# WiFi_Switch.net
KiCad netlist of a schematic drawn in EAGLE
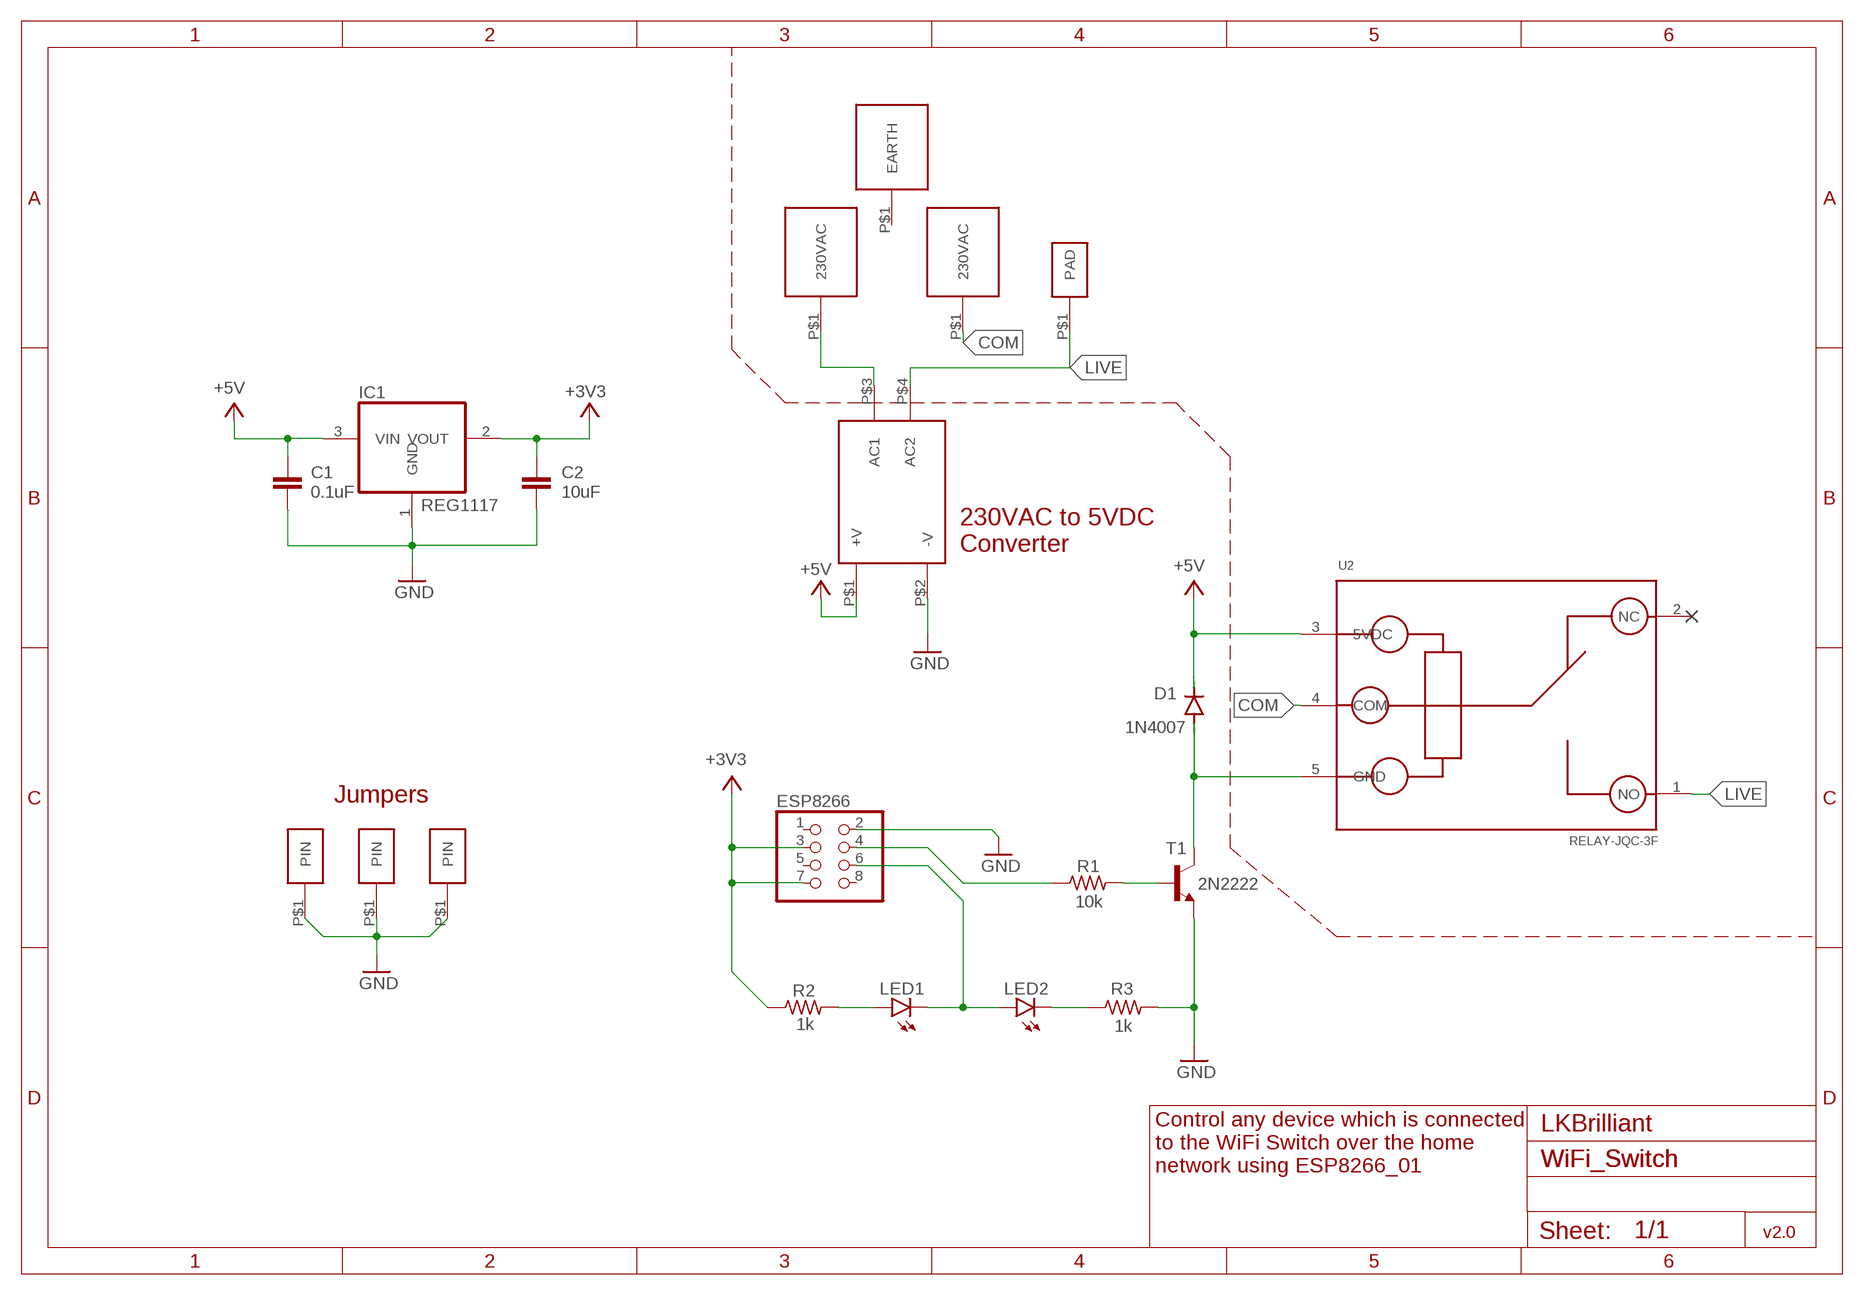
[diagram p0: schematic, sheet 1]

(export (version "E")
  (design (tool "Eeschema 10.0.6"))
  (components
    (comp (ref "C1")
      (value "0.1uF")
      (footprint "eagle-import:C0805")
      (libsource (lib "eagle-import") (part "C-EUC0805"))
    )
    (comp (ref "C2")
      (value "10uF")
      (footprint "eagle-import:C0805")
      (libsource (lib "eagle-import") (part "C-EUC0805"))
    )
    (comp (ref "D1")
      (value "1N4007")
      (footprint "eagle-import:DO214AC")
      (libsource (lib "eagle-import") (part "DIODE-DO214AC"))
    )
    (comp (ref "ESP8266")
      (value "PINHD-2X4")
      (footprint "eagle-import:2X04")
      (libsource (lib "eagle-import") (part "PINHD-2X4"))
    )
    (comp (ref "GND")
      (value "1-PIN")
      (footprint "eagle-import:1-PIN")
      (libsource (lib "eagle-import") (part "1-PIN"))
    )
    (comp (ref "IC1")
      (value "REG1117")
      (footprint "eagle-import:SOT223")
      (libsource (lib "eagle-import") (part "REG1117"))
    )
    (comp (ref "L")
      (value "230VAC_PAD")
      (footprint "eagle-import:11X9_SMD_PAD")
      (libsource (lib "eagle-import") (part "230VAC_PAD"))
    )
    (comp (ref "LED1")
      (value "LEDCHIPLED_0603")
      (footprint "eagle-import:CHIPLED_0603")
      (libsource (lib "eagle-import") (part "LEDCHIPLED_0603"))
    )
    (comp (ref "LED2")
      (value "LEDCHIPLED_0603")
      (footprint "eagle-import:CHIPLED_0603")
      (libsource (lib "eagle-import") (part "LEDCHIPLED_0603"))
    )
    (comp (ref "N")
      (value "230VAC_PAD")
      (footprint "eagle-import:11X9_SMD_PAD")
      (libsource (lib "eagle-import") (part "230VAC_PAD"))
    )
    (comp (ref "R1")
      (value "10k")
      (footprint "eagle-import:R0805")
      (libsource (lib "eagle-import") (part "R-US_R0805"))
    )
    (comp (ref "R2")
      (value "1k")
      (footprint "eagle-import:R0805")
      (libsource (lib "eagle-import") (part "R-US_R0805"))
    )
    (comp (ref "R3")
      (value "1k")
      (footprint "eagle-import:R0805")
      (libsource (lib "eagle-import") (part "R-US_R0805"))
    )
    (comp (ref "T1")
      (value "2N2222")
      (footprint "eagle-import:SOT23-EBC")
      (libsource (lib "eagle-import") (part "-NPN-SOT23-EBC"))
    )
    (comp (ref "U$1")
      (value "1-PIN")
      (footprint "eagle-import:1-PIN")
      (libsource (lib "eagle-import") (part "1-PIN"))
    )
    (comp (ref "U$4")
      (value "EARTH_PAD")
      (footprint "eagle-import:17X8_PAD")
      (libsource (lib "eagle-import") (part "EARTH_PAD"))
    )
    (comp (ref "U$5")
      (value "EXT_PAD")
      (footprint "eagle-import:4X2_PAD")
      (libsource (lib "eagle-import") (part "EXT_PAD"))
    )
    (comp (ref "U$6")
      (value "1-PIN")
      (footprint "eagle-import:1-PIN")
      (libsource (lib "eagle-import") (part "1-PIN"))
    )
    (comp (ref "U1")
      (value "230VAC/5VDC_CONVERTER")
      (footprint "eagle-import:REG_BLOCK")
      (libsource (lib "eagle-import") (part "230VAC/5VDC_CONVERTER"))
    )
    (comp (ref "U2")
      (value "RELAY-JQC-3F")
      (footprint "eagle-import:JQC-3F")
      (libsource (lib "eagle-import") (part "RELAY-JQC-3F"))
    )
  )
  (nets
    (net (code "1") (name "+3V3") (class "Default")
      (node (ref "C2") (pin "1") (pinfunction "1_1") (pintype "passive"))
      (node (ref "ESP8266") (pin "3") (pinfunction "3_3") (pintype "passive"))
      (node (ref "ESP8266") (pin "7") (pinfunction "7_7") (pintype "passive"))
      (node (ref "IC1") (pin "2") (pinfunction "VOUT_2") (pintype "output"))
      (node (ref "R2") (pin "1") (pinfunction "1_1") (pintype "passive"))
    )
    (net (code "2") (name "+5V") (class "Default")
      (node (ref "C1") (pin "1") (pinfunction "1_1") (pintype "passive"))
      (node (ref "D1") (pin "C") (pinfunction "C_C") (pintype "passive"))
      (node (ref "IC1") (pin "3") (pinfunction "VIN_3") (pintype "input"))
      (node (ref "U1") (pin "P$1") (pinfunction "+V_P$1") (pintype "bidirectional"))
      (node (ref "U2") (pin "3") (pinfunction "5VDC_3") (pintype "bidirectional"))
    )
    (net (code "3") (name "COM") (class "Default")
      (node (ref "L") (pin "P$1") (pinfunction "230VAC_P$1") (pintype "bidirectional"))
      (node (ref "U2") (pin "4") (pinfunction "COM_4") (pintype "bidirectional"))
    )
    (net (code "4") (name "GND") (class "Default")
      (node (ref "C1") (pin "2") (pinfunction "2_2") (pintype "passive"))
      (node (ref "C2") (pin "2") (pinfunction "2_2") (pintype "passive"))
      (node (ref "ESP8266") (pin "2") (pinfunction "2_2") (pintype "passive"))
      (node (ref "GND") (pin "P$1") (pinfunction "PIN_P$1") (pintype "bidirectional"))
      (node (ref "IC1") (pin "1") (pinfunction "GND_1") (pintype "power_in"))
      (node (ref "R3") (pin "2") (pinfunction "2_2") (pintype "passive"))
      (node (ref "T1") (pin "E") (pinfunction "E_E") (pintype "passive"))
      (node (ref "U$1") (pin "P$1") (pinfunction "PIN_P$1") (pintype "bidirectional"))
      (node (ref "U$6") (pin "P$1") (pinfunction "PIN_P$1") (pintype "bidirectional"))
      (node (ref "U1") (pin "P$2") (pinfunction "-V_P$2") (pintype "bidirectional"))
    )
    (net (code "5") (name "LIVE") (class "Default")
      (node (ref "U$5") (pin "P$1") (pinfunction "PAD_P$1") (pintype "bidirectional"))
      (node (ref "U1") (pin "P$4") (pinfunction "AC2_P$4") (pintype "bidirectional"))
      (node (ref "U2") (pin "1") (pinfunction "NO_1") (pintype "bidirectional"))
    )
    (net (code "6") (name "Net-(ESP8266-Pad4)") (class "Default")
      (node (ref "ESP8266") (pin "4") (pinfunction "4_4") (pintype "passive"))
      (node (ref "R1") (pin "1") (pinfunction "1_1") (pintype "passive"))
    )
    (net (code "7") (name "Net-(ESP8266-Pad6)") (class "Default")
      (node (ref "ESP8266") (pin "6") (pinfunction "6_6") (pintype "passive"))
      (node (ref "LED1") (pin "C") (pinfunction "C_C") (pintype "passive"))
      (node (ref "LED2") (pin "A") (pinfunction "A_A") (pintype "passive"))
    )
    (net (code "8") (name "Net-(LED1-PadA)") (class "Default")
      (node (ref "LED1") (pin "A") (pinfunction "A_A") (pintype "passive"))
      (node (ref "R2") (pin "2") (pinfunction "2_2") (pintype "passive"))
    )
    (net (code "9") (name "Net-(LED2-PadC)") (class "Default")
      (node (ref "LED2") (pin "C") (pinfunction "C_C") (pintype "passive"))
      (node (ref "R3") (pin "1") (pinfunction "1_1") (pintype "passive"))
    )
    (net (code "10") (name "Net-(N-230VAC)") (class "Default")
      (node (ref "N") (pin "P$1") (pinfunction "230VAC_P$1") (pintype "bidirectional"))
      (node (ref "U1") (pin "P$3") (pinfunction "AC1_P$3") (pintype "bidirectional"))
    )
    (net (code "11") (name "Net-(R1-Pad2)") (class "Default")
      (node (ref "R1") (pin "2") (pinfunction "2_2") (pintype "passive"))
      (node (ref "T1") (pin "B") (pinfunction "B_B") (pintype "passive"))
    )
    (net (code "12") (name "Net-(U2-GND)") (class "Default")
      (node (ref "D1") (pin "A") (pinfunction "A_A") (pintype "passive"))
      (node (ref "T1") (pin "C") (pinfunction "C_C") (pintype "passive"))
      (node (ref "U2") (pin "5") (pinfunction "GND_5") (pintype "bidirectional"))
    )
    (net (code "13") (name "unconnected-(ESP8266-Pad1)") (class "Default")
      (node (ref "ESP8266") (pin "1") (pinfunction "1_1") (pintype "passive"))
    )
    (net (code "14") (name "unconnected-(ESP8266-Pad5)") (class "Default")
      (node (ref "ESP8266") (pin "5") (pinfunction "5_5") (pintype "passive"))
    )
    (net (code "15") (name "unconnected-(ESP8266-Pad8)") (class "Default")
      (node (ref "ESP8266") (pin "8") (pinfunction "8_8") (pintype "passive"))
    )
    (net (code "16") (name "unconnected-(U$4-EARTH-PadP$1)") (class "Default")
      (node (ref "U$4") (pin "P$1") (pinfunction "EARTH_P$1") (pintype "bidirectional"))
    )
    (net (code "17") (name "unconnected-(U2-NC-Pad2)") (class "Default")
      (node (ref "U2") (pin "2") (pinfunction "NC_2") (pintype "bidirectional"))
    )
  )
)
